# EveryCook_Mainboard.net
KiCad netlist of a schematic drawn in EAGLE
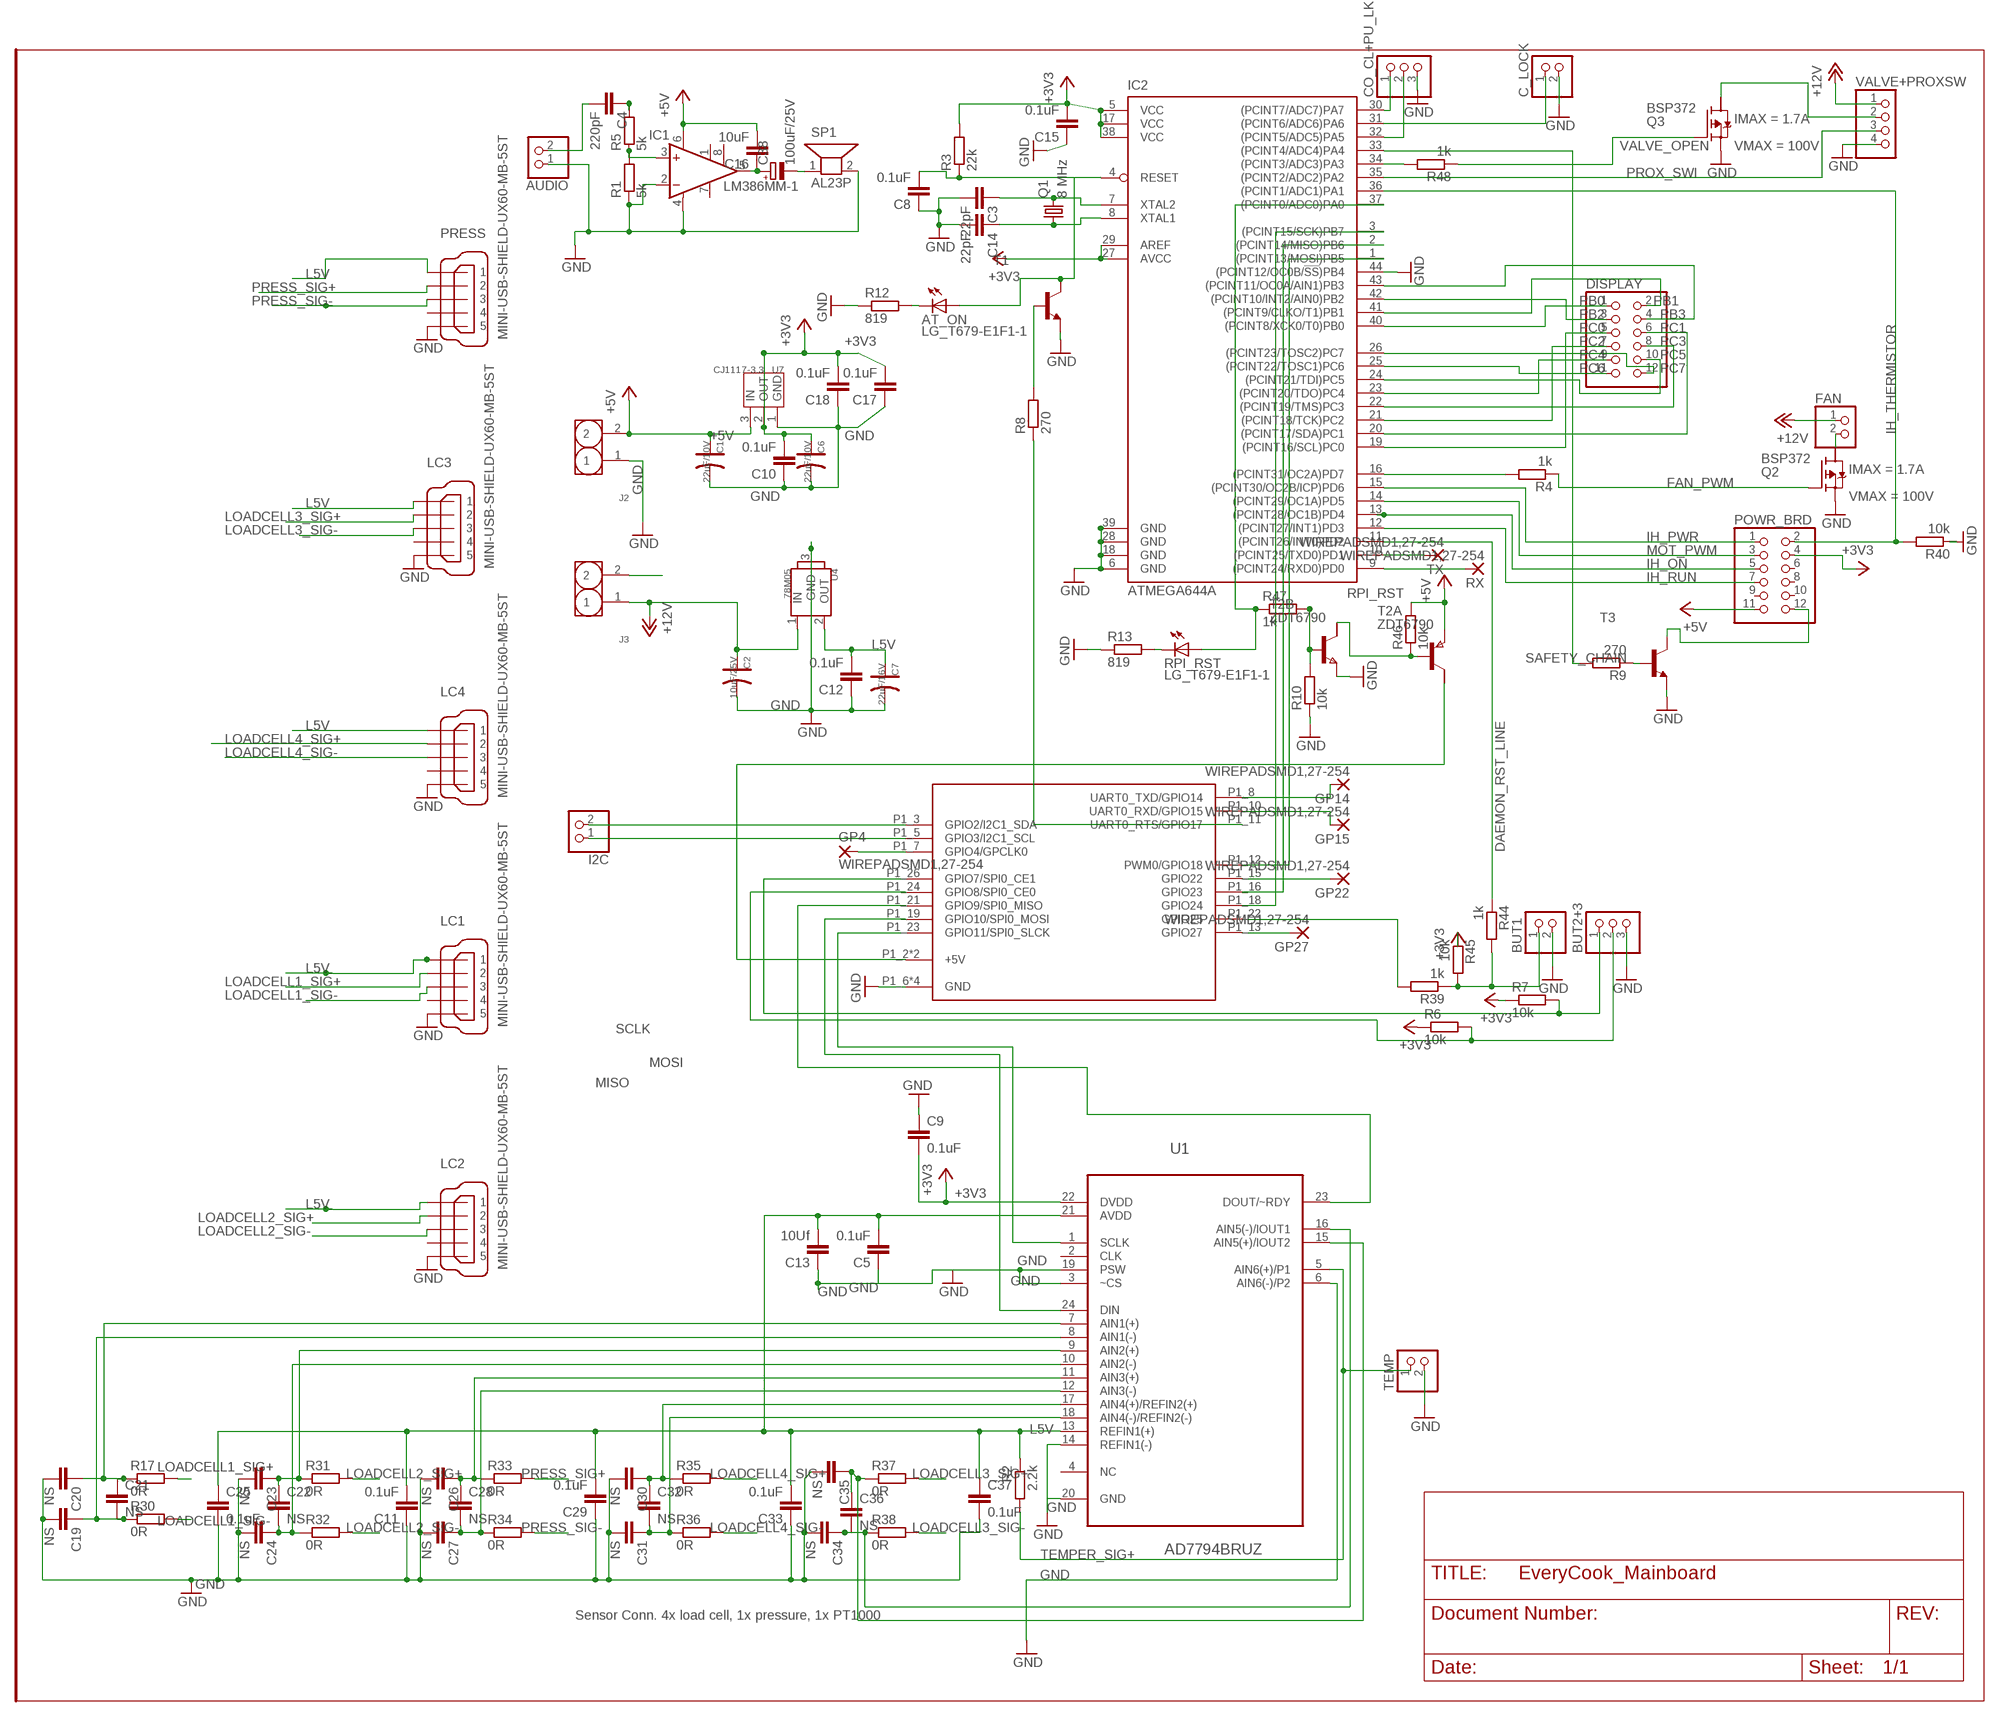
[diagram p0: schematic, sheet 1]

(export (version "E")
  (design (tool "Eeschema 10.0.6"))
  (components
    (comp (ref "AT_ON")
      (value "LG_T679-E1F1-1")
      (footprint "eagle-import:PLCC2")
      (libsource (lib "eagle-import") (part "_T679-?-1E1F1LG"))
    )
    (comp (ref "AUDIO")
      (value "PINHD-1X2")
      (footprint "eagle-import:1X02")
      (libsource (lib "eagle-import") (part "PINHD-1X2"))
    )
    (comp (ref "BUT1")
      (value "PINHD-1X2")
      (footprint "eagle-import:1X02")
      (libsource (lib "eagle-import") (part "PINHD-1X2"))
    )
    (comp (ref "BUT2+3")
      (value "PINHD-1X3")
      (footprint "eagle-import:1X03")
      (libsource (lib "eagle-import") (part "PINHD-1X3"))
    )
    (comp (ref "C1")
      (value "22uF/10V")
      (footprint "eagle-import:AVX-A")
      (libsource (lib "eagle-import") (part "CAP-AVX-A"))
    )
    (comp (ref "C2")
      (value "10uF/25V")
      (footprint "eagle-import:ELECTRO-SMD-B-4.8MM")
      (libsource (lib "eagle-import") (part "CAP-ELECTRO-B"))
    )
    (comp (ref "C3")
      (value "22pF")
      (footprint "eagle-import:C0805")
      (libsource (lib "eagle-import") (part "C-EUC0805"))
    )
    (comp (ref "C4")
      (value "220pF")
      (footprint "eagle-import:C0805")
      (libsource (lib "eagle-import") (part "C-EUC0805"))
    )
    (comp (ref "C5")
      (value "0.1uF")
      (footprint "eagle-import:C0805")
      (libsource (lib "eagle-import") (part "C-EUC0805"))
    )
    (comp (ref "C6")
      (value "22uF/10V")
      (footprint "eagle-import:AVX-A")
      (libsource (lib "eagle-import") (part "CAP-AVX-A"))
    )
    (comp (ref "C7")
      (value "22uF/16V")
      (footprint "eagle-import:ELECTRO-SMD-B-4.8MM")
      (libsource (lib "eagle-import") (part "CAP-ELECTRO-B"))
    )
    (comp (ref "C8")
      (value "0.1uF")
      (footprint "eagle-import:C0805")
      (libsource (lib "eagle-import") (part "C-EUC0805"))
    )
    (comp (ref "C9")
      (value "0.1uF")
      (footprint "eagle-import:C0805")
      (libsource (lib "eagle-import") (part "C-EUC0805"))
    )
    (comp (ref "C10")
      (value "0.1uF")
      (footprint "eagle-import:C0805")
      (libsource (lib "eagle-import") (part "C-EUC0805"))
    )
    (comp (ref "C11")
      (value "0.1uF")
      (footprint "eagle-import:C0805")
      (libsource (lib "eagle-import") (part "C-EUC0805"))
    )
    (comp (ref "C12")
      (value "0.1uF")
      (footprint "eagle-import:C0805")
      (libsource (lib "eagle-import") (part "C-EUC0805"))
    )
    (comp (ref "C13")
      (value "10Uf")
      (footprint "eagle-import:C0805")
      (libsource (lib "eagle-import") (part "C-EUC0805"))
    )
    (comp (ref "C14")
      (value "22pF")
      (footprint "eagle-import:C0805")
      (libsource (lib "eagle-import") (part "C-EUC0805"))
    )
    (comp (ref "C15")
      (value "0.1uF")
      (footprint "eagle-import:C0805")
      (libsource (lib "eagle-import") (part "C-EUC0805"))
    )
    (comp (ref "C16")
      (value "10uF")
      (footprint "eagle-import:C0805")
      (libsource (lib "eagle-import") (part "C-EUC0805"))
    )
    (comp (ref "C17")
      (value "0.1uF")
      (footprint "eagle-import:C0805")
      (libsource (lib "eagle-import") (part "C-EUC0805"))
    )
    (comp (ref "C18")
      (value "0.1uF")
      (footprint "eagle-import:C0805")
      (libsource (lib "eagle-import") (part "C-EUC0805"))
    )
    (comp (ref "C19")
      (value "NS")
      (footprint "eagle-import:C0805")
      (libsource (lib "eagle-import") (part "C-EUC0805"))
    )
    (comp (ref "C20")
      (value "NS")
      (footprint "eagle-import:C0805")
      (libsource (lib "eagle-import") (part "C-EUC0805"))
    )
    (comp (ref "C21")
      (value "NS")
      (footprint "eagle-import:C0805")
      (libsource (lib "eagle-import") (part "C-EUC0805"))
    )
    (comp (ref "C22")
      (value "NS")
      (footprint "eagle-import:C0805")
      (libsource (lib "eagle-import") (part "C-EUC0805"))
    )
    (comp (ref "C23")
      (value "NS")
      (footprint "eagle-import:C0805")
      (libsource (lib "eagle-import") (part "C-EUC0805"))
    )
    (comp (ref "C24")
      (value "NS")
      (footprint "eagle-import:C0805")
      (libsource (lib "eagle-import") (part "C-EUC0805"))
    )
    (comp (ref "C25")
      (value "0.1uF")
      (footprint "eagle-import:C0805")
      (libsource (lib "eagle-import") (part "C-EUC0805"))
    )
    (comp (ref "C26")
      (value "NS")
      (footprint "eagle-import:C0805")
      (libsource (lib "eagle-import") (part "C-EUC0805"))
    )
    (comp (ref "C27")
      (value "NS")
      (footprint "eagle-import:C0805")
      (libsource (lib "eagle-import") (part "C-EUC0805"))
    )
    (comp (ref "C28")
      (value "NS")
      (footprint "eagle-import:C0805")
      (libsource (lib "eagle-import") (part "C-EUC0805"))
    )
    (comp (ref "C29")
      (value "0.1uF")
      (footprint "eagle-import:C0805")
      (libsource (lib "eagle-import") (part "C-EUC0805"))
    )
    (comp (ref "C30")
      (value "NS")
      (footprint "eagle-import:C0805")
      (libsource (lib "eagle-import") (part "C-EUC0805"))
    )
    (comp (ref "C31")
      (value "NS")
      (footprint "eagle-import:C0805")
      (libsource (lib "eagle-import") (part "C-EUC0805"))
    )
    (comp (ref "C32")
      (value "NS")
      (footprint "eagle-import:C0805")
      (libsource (lib "eagle-import") (part "C-EUC0805"))
    )
    (comp (ref "C33")
      (value "0.1uF")
      (footprint "eagle-import:C0805")
      (libsource (lib "eagle-import") (part "C-EUC0805"))
    )
    (comp (ref "C34")
      (value "NS")
      (footprint "eagle-import:C0805")
      (libsource (lib "eagle-import") (part "C-EUC0805"))
    )
    (comp (ref "C35")
      (value "NS")
      (footprint "eagle-import:C0805")
      (libsource (lib "eagle-import") (part "C-EUC0805"))
    )
    (comp (ref "C36")
      (value "NS")
      (footprint "eagle-import:C0805")
      (libsource (lib "eagle-import") (part "C-EUC0805"))
    )
    (comp (ref "C37")
      (value "0.1uF")
      (footprint "eagle-import:C0805")
      (libsource (lib "eagle-import") (part "C-EUC0805"))
    )
    (comp (ref "C38")
      (value "100uF/25V")
      (footprint "eagle-import:UD-6,3X7,7_NICHICON")
      (libsource (lib "eagle-import") (part "CPOL-EUUD-6,3X7,7"))
    )
    (comp (ref "CO_CL+PU_LK")
      (value "PINHD-1X3")
      (footprint "eagle-import:1X03")
      (libsource (lib "eagle-import") (part "PINHD-1X3"))
    )
    (comp (ref "C_LOCK")
      (value "PINHD-1X2")
      (footprint "eagle-import:1X02")
      (libsource (lib "eagle-import") (part "PINHD-1X2"))
    )
    (comp (ref "DISPLAY")
      (value "PINHD-2X6")
      (footprint "eagle-import:2X06")
      (libsource (lib "eagle-import") (part "PINHD-2X6"))
    )
    (comp (ref "FAN")
      (value "PINHD-1X2")
      (footprint "eagle-import:1X02")
      (libsource (lib "eagle-import") (part "PINHD-1X2"))
    )
    (comp (ref "GP4")
      (value "WIREPADSMD1,27-254")
      (footprint "eagle-import:SMD1,27-2,54")
      (libsource (lib "eagle-import") (part "WIREPADSMD1,27-254"))
    )
    (comp (ref "GP14")
      (value "WIREPADSMD1,27-254")
      (footprint "eagle-import:SMD1,27-2,54")
      (libsource (lib "eagle-import") (part "WIREPADSMD1,27-254"))
    )
    (comp (ref "GP15")
      (value "WIREPADSMD1,27-254")
      (footprint "eagle-import:SMD1,27-2,54")
      (libsource (lib "eagle-import") (part "WIREPADSMD1,27-254"))
    )
    (comp (ref "GP22")
      (value "WIREPADSMD1,27-254")
      (footprint "eagle-import:SMD1,27-2,54")
      (libsource (lib "eagle-import") (part "WIREPADSMD1,27-254"))
    )
    (comp (ref "GP27")
      (value "WIREPADSMD1,27-254")
      (footprint "eagle-import:SMD1,27-2,54")
      (libsource (lib "eagle-import") (part "WIREPADSMD1,27-254"))
    )
    (comp (ref "I2C")
      (value "PINHD-1X2")
      (footprint "eagle-import:1X02")
      (libsource (lib "eagle-import") (part "PINHD-1X2"))
    )
    (comp (ref "IC1")
      (value "LM386MM-1")
      (footprint "eagle-import:MMSOP08")
      (libsource (lib "eagle-import") (part "LM386?-MM1"))
    )
    (comp (ref "IC2")
      (value "ATMEGA644A")
      (footprint "eagle-import:TQFP44")
      (fields (field (name "MPN") "ATMEGA644PV-10AU"))
      (libsource (lib "eagle-import") (part "ATMEGA644A"))
    )
    (comp (ref "J2")
      (value "HEADER-2P-5.0")
      (footprint "eagle-import:2P-5.0")
      (libsource (lib "eagle-import") (part "HEADER-2P-5.0"))
    )
    (comp (ref "J3")
      (value "HEADER-2P-5.0")
      (footprint "eagle-import:2P-5.0")
      (libsource (lib "eagle-import") (part "HEADER-2P-5.0"))
    )
    (comp (ref "LC1")
      (value "MINI-USB-SHIELD-UX60-MB-5ST")
      (footprint "eagle-import:UX60-MB-5ST")
      (libsource (lib "eagle-import") (part "MINI-USB-SHIELD-UX60-MB-5ST"))
    )
    (comp (ref "LC2")
      (value "MINI-USB-SHIELD-UX60-MB-5ST")
      (footprint "eagle-import:UX60-MB-5ST")
      (libsource (lib "eagle-import") (part "MINI-USB-SHIELD-UX60-MB-5ST"))
    )
    (comp (ref "LC3")
      (value "MINI-USB-SHIELD-UX60-MB-5ST")
      (footprint "eagle-import:UX60-MB-5ST")
      (libsource (lib "eagle-import") (part "MINI-USB-SHIELD-UX60-MB-5ST"))
    )
    (comp (ref "LC4")
      (value "MINI-USB-SHIELD-UX60-MB-5ST")
      (footprint "eagle-import:UX60-MB-5ST")
      (libsource (lib "eagle-import") (part "MINI-USB-SHIELD-UX60-MB-5ST"))
    )
    (comp (ref "POWR_BRD")
      (value "PINHD-2X6")
      (footprint "eagle-import:2X06")
      (libsource (lib "eagle-import") (part "PINHD-2X6"))
    )
    (comp (ref "PRESS")
      (value "MINI-USB-SHIELD-UX60-MB-5ST")
      (footprint "eagle-import:UX60-MB-5ST")
      (libsource (lib "eagle-import") (part "MINI-USB-SHIELD-UX60-MB-5ST"))
    )
    (comp (ref "Q1")
      (value "8 MHz")
      (footprint "eagle-import:HC49UP")
      (libsource (lib "eagle-import") (part "CRYSTALHC49UP"))
    )
    (comp (ref "Q2")
      (value "BSP372")
      (footprint "eagle-import:PG-SOT-223")
      (fields (field (name "IMAX") "1.7A") (field (name "MF") "Infineon") (field (name "VMAX") "100V"))
      (libsource (lib "eagle-import") (part "BSP613P"))
    )
    (comp (ref "Q3")
      (value "BSP372")
      (footprint "eagle-import:PG-SOT-223")
      (fields (field (name "IMAX") "1.7A") (field (name "MF") "Infineon") (field (name "VMAX") "100V"))
      (libsource (lib "eagle-import") (part "BSP613P"))
    )
    (comp (ref "R1")
      (value "5k")
      (footprint "eagle-import:R0805")
      (libsource (lib "eagle-import") (part "R-EU_R0805"))
    )
    (comp (ref "R2")
      (value "2.2k")
      (footprint "eagle-import:R0805")
      (libsource (lib "eagle-import") (part "R-EU_R0805"))
    )
    (comp (ref "R3")
      (value "22k")
      (footprint "eagle-import:R0805")
      (libsource (lib "eagle-import") (part "R-EU_R0805"))
    )
    (comp (ref "R4")
      (value "1k")
      (footprint "eagle-import:R0805")
      (libsource (lib "eagle-import") (part "R-EU_R0805"))
    )
    (comp (ref "R5")
      (value "5k")
      (footprint "eagle-import:R0805")
      (libsource (lib "eagle-import") (part "R-EU_R0805"))
    )
    (comp (ref "R6")
      (value "10k")
      (footprint "eagle-import:R0805")
      (libsource (lib "eagle-import") (part "R-EU_R0805"))
    )
    (comp (ref "R7")
      (value "10k")
      (footprint "eagle-import:R0805")
      (libsource (lib "eagle-import") (part "R-EU_R0805"))
    )
    (comp (ref "R8")
      (value "270")
      (footprint "eagle-import:R0805")
      (libsource (lib "eagle-import") (part "R-EU_R0805"))
    )
    (comp (ref "R9")
      (value "270")
      (footprint "eagle-import:R0805")
      (libsource (lib "eagle-import") (part "R-EU_R0805"))
    )
    (comp (ref "R10")
      (value "10k")
      (footprint "eagle-import:R0805")
      (libsource (lib "eagle-import") (part "R-EU_R0805"))
    )
    (comp (ref "R12")
      (value "819")
      (footprint "eagle-import:R0805")
      (libsource (lib "eagle-import") (part "R-EU_R0805"))
    )
    (comp (ref "R13")
      (value "819")
      (footprint "eagle-import:R0805")
      (libsource (lib "eagle-import") (part "R-EU_R0805"))
    )
    (comp (ref "R17")
      (value "0R")
      (footprint "eagle-import:R0805")
      (libsource (lib "eagle-import") (part "R-EU_R0805"))
    )
    (comp (ref "R30")
      (value "0R")
      (footprint "eagle-import:R0805")
      (libsource (lib "eagle-import") (part "R-EU_R0805"))
    )
    (comp (ref "R31")
      (value "0R")
      (footprint "eagle-import:R0805")
      (libsource (lib "eagle-import") (part "R-EU_R0805"))
    )
    (comp (ref "R32")
      (value "0R")
      (footprint "eagle-import:R0805")
      (libsource (lib "eagle-import") (part "R-EU_R0805"))
    )
    (comp (ref "R33")
      (value "0R")
      (footprint "eagle-import:R0805")
      (libsource (lib "eagle-import") (part "R-EU_R0805"))
    )
    (comp (ref "R34")
      (value "0R")
      (footprint "eagle-import:R0805")
      (libsource (lib "eagle-import") (part "R-EU_R0805"))
    )
    (comp (ref "R35")
      (value "0R")
      (footprint "eagle-import:R0805")
      (libsource (lib "eagle-import") (part "R-EU_R0805"))
    )
    (comp (ref "R36")
      (value "0R")
      (footprint "eagle-import:R0805")
      (libsource (lib "eagle-import") (part "R-EU_R0805"))
    )
    (comp (ref "R37")
      (value "0R")
      (footprint "eagle-import:R0805")
      (libsource (lib "eagle-import") (part "R-EU_R0805"))
    )
    (comp (ref "R38")
      (value "0R")
      (footprint "eagle-import:R0805")
      (libsource (lib "eagle-import") (part "R-EU_R0805"))
    )
    (comp (ref "R39")
      (value "1k")
      (footprint "eagle-import:R0805")
      (libsource (lib "eagle-import") (part "R-EU_R0805"))
    )
    (comp (ref "R40")
      (value "10k")
      (footprint "eagle-import:R0805")
      (libsource (lib "eagle-import") (part "R-EU_R0805"))
    )
    (comp (ref "R44")
      (value "1k")
      (footprint "eagle-import:R0805")
      (libsource (lib "eagle-import") (part "R-EU_R0805"))
    )
    (comp (ref "R45")
      (value "10k")
      (footprint "eagle-import:R0805")
      (libsource (lib "eagle-import") (part "R-EU_R0805"))
    )
    (comp (ref "R46")
      (value "10k")
      (footprint "eagle-import:R0805")
      (libsource (lib "eagle-import") (part "R-EU_R0805"))
    )
    (comp (ref "R47")
      (value "1k")
      (footprint "eagle-import:R0805")
      (libsource (lib "eagle-import") (part "R-EU_R0805"))
    )
    (comp (ref "R48")
      (value "1k")
      (footprint "eagle-import:R0805")
      (libsource (lib "eagle-import") (part "R-EU_R0805"))
    )
    (comp (ref "RPI_RST")
      (value "LG_T679-E1F1-1")
      (footprint "eagle-import:PLCC2")
      (libsource (lib "eagle-import") (part "_T679-?-1E1F1LG"))
    )
    (comp (ref "RX")
      (value "WIREPADSMD1,27-254")
      (footprint "eagle-import:SMD1,27-2,54")
      (libsource (lib "eagle-import") (part "WIREPADSMD1,27-254"))
    )
    (comp (ref "SP1")
      (value "AL23P")
      (footprint "eagle-import:AL23P")
      (libsource (lib "eagle-import") (part "AL23P"))
    )
    (comp (ref "T1")
      (value "MMBT2222ALT1-NPN-SOT23-BEC")
      (footprint "eagle-import:SOT23-BEC")
      (libsource (lib "eagle-import") (part "-NPN-SOT23-BECMMBT2222ALT1"))
    )
    (comp (ref "T2")
      (value "ZDT6790")
      (footprint "eagle-import:SM8")
      (libsource (lib "eagle-import") (part "NPN_PNPSM8"))
    )
    (comp (ref "T3")
      (value "MMBT2222ALT1-NPN-SOT23-BEC")
      (footprint "eagle-import:SOT23-BEC")
      (libsource (lib "eagle-import") (part "-NPN-SOT23-BECMMBT2222ALT1"))
    )
    (comp (ref "TEMP")
      (value "PINHD-1X2")
      (footprint "eagle-import:1X02")
      (libsource (lib "eagle-import") (part "PINHD-1X2"))
    )
    (comp (ref "TX")
      (value "WIREPADSMD1,27-254")
      (footprint "eagle-import:SMD1,27-2,54")
      (libsource (lib "eagle-import") (part "WIREPADSMD1,27-254"))
    )
    (comp (ref "U$5")
      (value "RPI-B-V2")
      (footprint "eagle-import:RPI-B-V2")
      (libsource (lib "eagle-import") (part "RPI-B-V2"))
    )
    (comp (ref "U1")
      (value "AD7794BRUZ")
      (footprint "eagle-import:SOP65P640X120-24N")
      (libsource (lib "eagle-import") (part "AD7794BRUZ"))
    )
    (comp (ref "U4")
      (value "78M05")
      (footprint "eagle-import:TO252")
      (libsource (lib "eagle-import") (part "78M05-TO252"))
    )
    (comp (ref "U7")
      (value "CJ1117-3.3")
      (footprint "eagle-import:SOT89")
      (libsource (lib "eagle-import") (part "LD1117SOT89"))
    )
    (comp (ref "VALVE+PROXSW")
      (value "PINHD-1X4")
      (footprint "eagle-import:1X04")
      (libsource (lib "eagle-import") (part "PINHD-1X4"))
    )
  )
  (nets
    (net (code "1") (name "+3V3") (class "Default")
      (node (ref "C10") (pin "2") (pinfunction "2_2") (pintype "passive"))
      (node (ref "C15") (pin "2") (pinfunction "2_2") (pintype "passive"))
      (node (ref "C17") (pin "2") (pinfunction "2_2") (pintype "passive"))
      (node (ref "C18") (pin "2") (pinfunction "2_2") (pintype "passive"))
      (node (ref "C6") (pin "+") (pinfunction "+_+") (pintype "passive"))
      (node (ref "C9") (pin "2") (pinfunction "2_2") (pintype "passive"))
      (node (ref "IC2") (pin "17") (pinfunction "VCC_17") (pintype "power_in"))
      (node (ref "IC2") (pin "27") (pinfunction "AVCC_27") (pintype "power_in"))
      (node (ref "IC2") (pin "29") (pinfunction "AREF_29") (pintype "passive"))
      (node (ref "IC2") (pin "38") (pinfunction "VCC_38") (pintype "power_in"))
      (node (ref "IC2") (pin "5") (pinfunction "VCC_5") (pintype "power_in"))
      (node (ref "POWR_BRD") (pin "4") (pinfunction "4_4") (pintype "passive"))
      (node (ref "R3") (pin "2") (pinfunction "2_2") (pintype "passive"))
      (node (ref "R45") (pin "1") (pinfunction "1_1") (pintype "passive"))
      (node (ref "R6") (pin "1") (pinfunction "1_1") (pintype "passive"))
      (node (ref "R7") (pin "1") (pinfunction "1_1") (pintype "passive"))
      (node (ref "U1") (pin "22") (pinfunction "DVDD_22") (pintype "power_in"))
      (node (ref "U7") (pin "2") (pinfunction "OUT_2") (pintype "bidirectional"))
      (node (ref "U7") (pin "4") (pinfunction "TAB_4") (pintype "bidirectional"))
    )
    (net (code "2") (name "+5V") (class "Default")
      (node (ref "C1") (pin "+") (pinfunction "+_+") (pintype "passive"))
      (node (ref "C16") (pin "2") (pinfunction "2_2") (pintype "passive"))
      (node (ref "IC1") (pin "6") (pinfunction "VS_6") (pintype "power_in"))
      (node (ref "J2") (pin "2") (pinfunction "2_2") (pintype "bidirectional"))
      (node (ref "POWR_BRD") (pin "11") (pinfunction "11_11") (pintype "passive"))
      (node (ref "R46") (pin "2") (pinfunction "2_2") (pintype "passive"))
      (node (ref "T2") (pin "1") (pinfunction "E_1") (pintype "passive"))
      (node (ref "U7") (pin "3") (pinfunction "IN_3") (pintype "bidirectional"))
    )
    (net (code "3") (name "+12V") (class "Default")
      (node (ref "C2") (pin "+") (pinfunction "+_+") (pintype "passive"))
      (node (ref "FAN") (pin "1") (pinfunction "1_1") (pintype "passive"))
      (node (ref "J3") (pin "1") (pinfunction "1_1") (pintype "bidirectional"))
      (node (ref "U4") (pin "1") (pinfunction "IN_1") (pintype "bidirectional"))
      (node (ref "VALVE+PROXSW") (pin "1") (pinfunction "1_1") (pintype "passive"))
    )
    (net (code "4") (name "/DAEMON_RST_LINE") (class "Default")
      (node (ref "IC2") (pin "11") (pinfunction "(PCINT26/INT0)PD2_11") (pintype "bidirectional"))
      (node (ref "R44") (pin "1") (pinfunction "1_1") (pintype "passive"))
    )
    (net (code "5") (name "/FAN_PWM") (class "Default")
      (node (ref "Q2") (pin "1") (pinfunction "G_1") (pintype "passive"))
      (node (ref "R4") (pin "1") (pinfunction "1_1") (pintype "passive"))
    )
    (net (code "6") (name "/IH_ON") (class "Default")
      (node (ref "IC2") (pin "13") (pinfunction "(PCINT28/OC1B)PD4_13") (pintype "bidirectional"))
      (node (ref "POWR_BRD") (pin "5") (pinfunction "5_5") (pintype "passive"))
    )
    (net (code "7") (name "/IH_PWR") (class "Default")
      (node (ref "IC2") (pin "15") (pinfunction "(PCINT30/OC2B/ICP)PD6_15") (pintype "bidirectional"))
      (node (ref "POWR_BRD") (pin "1") (pinfunction "1_1") (pintype "passive"))
    )
    (net (code "8") (name "/IH_RUN") (class "Default")
      (node (ref "IC2") (pin "12") (pinfunction "(PCINT27/INT1)PD3_12") (pintype "bidirectional"))
      (node (ref "POWR_BRD") (pin "7") (pinfunction "7_7") (pintype "passive"))
    )
    (net (code "9") (name "/IH_THERMISTOR") (class "Default")
      (node (ref "IC2") (pin "36") (pinfunction "(PCINT1/ADC1)PA1_36") (pintype "bidirectional"))
      (node (ref "POWR_BRD") (pin "2") (pinfunction "2_2") (pintype "passive"))
      (node (ref "R40") (pin "2") (pinfunction "2_2") (pintype "passive"))
    )
    (net (code "10") (name "/L5V") (class "Default")
      (node (ref "C11") (pin "2") (pinfunction "2_2") (pintype "passive"))
      (node (ref "C12") (pin "2") (pinfunction "2_2") (pintype "passive"))
      (node (ref "C13") (pin "2") (pinfunction "2_2") (pintype "passive"))
      (node (ref "C25") (pin "1") (pinfunction "1_1") (pintype "passive"))
      (node (ref "C29") (pin "2") (pinfunction "2_2") (pintype "passive"))
      (node (ref "C33") (pin "2") (pinfunction "2_2") (pintype "passive"))
      (node (ref "C37") (pin "1") (pinfunction "1_1") (pintype "passive"))
      (node (ref "C5") (pin "2") (pinfunction "2_2") (pintype "passive"))
      (node (ref "C7") (pin "+") (pinfunction "+_+") (pintype "passive"))
      (node (ref "LC1") (pin "1") (pinfunction "1_1") (pintype "input"))
      (node (ref "LC2") (pin "1") (pinfunction "1_1") (pintype "input"))
      (node (ref "LC3") (pin "1") (pinfunction "1_1") (pintype "input"))
      (node (ref "LC4") (pin "1") (pinfunction "1_1") (pintype "input"))
      (node (ref "PRESS") (pin "1") (pinfunction "1_1") (pintype "input"))
      (node (ref "R2") (pin "1") (pinfunction "1_1") (pintype "passive"))
      (node (ref "U1") (pin "13") (pinfunction "REFIN1(+)_13") (pintype "input"))
      (node (ref "U1") (pin "21") (pinfunction "AVDD_21") (pintype "power_in"))
      (node (ref "U4") (pin "2") (pinfunction "OUT_2") (pintype "bidirectional"))
    )
    (net (code "11") (name "/LOADCELL1_SIG+") (class "Default")
      (node (ref "LC1") (pin "2") (pinfunction "2_2") (pintype "input"))
      (node (ref "R17") (pin "2") (pinfunction "2_2") (pintype "passive"))
    )
    (net (code "12") (name "/LOADCELL1_SIG-") (class "Default")
      (node (ref "LC1") (pin "3") (pinfunction "3_3") (pintype "input"))
      (node (ref "R30") (pin "2") (pinfunction "2_2") (pintype "passive"))
    )
    (net (code "13") (name "/LOADCELL2_SIG+") (class "Default")
      (node (ref "LC2") (pin "2") (pinfunction "2_2") (pintype "input"))
      (node (ref "R31") (pin "2") (pinfunction "2_2") (pintype "passive"))
    )
    (net (code "14") (name "/LOADCELL2_SIG-") (class "Default")
      (node (ref "LC2") (pin "3") (pinfunction "3_3") (pintype "input"))
      (node (ref "R32") (pin "2") (pinfunction "2_2") (pintype "passive"))
    )
    (net (code "15") (name "/LOADCELL3_SIG+") (class "Default")
      (node (ref "LC3") (pin "2") (pinfunction "2_2") (pintype "input"))
      (node (ref "R37") (pin "2") (pinfunction "2_2") (pintype "passive"))
    )
    (net (code "16") (name "/LOADCELL3_SIG-") (class "Default")
      (node (ref "LC3") (pin "3") (pinfunction "3_3") (pintype "input"))
      (node (ref "R38") (pin "2") (pinfunction "2_2") (pintype "passive"))
    )
    (net (code "17") (name "/LOADCELL4_SIG+") (class "Default")
      (node (ref "LC4") (pin "2") (pinfunction "2_2") (pintype "input"))
      (node (ref "R35") (pin "2") (pinfunction "2_2") (pintype "passive"))
    )
    (net (code "18") (name "/LOADCELL4_SIG-") (class "Default")
      (node (ref "LC4") (pin "3") (pinfunction "3_3") (pintype "input"))
      (node (ref "R36") (pin "2") (pinfunction "2_2") (pintype "passive"))
    )
    (net (code "19") (name "/MISO") (class "Default")
      (node (ref "U$5") (pin "P1_21") (pinfunction "GPIO9/SPI0_MISO_P1_21") (pintype "bidirectional"))
      (node (ref "U1") (pin "23") (pinfunction "DOUT/~{RDY}_23") (pintype "bidirectional"))
    )
    (net (code "20") (name "/MOSI") (class "Default")
      (node (ref "U$5") (pin "P1_19") (pinfunction "GPIO10/SPI0_MOSI_P1_19") (pintype "bidirectional"))
      (node (ref "U1") (pin "24") (pinfunction "DIN_24") (pintype "input"))
    )
    (net (code "21") (name "/MOT_PWM") (class "Default")
      (node (ref "IC2") (pin "14") (pinfunction "(PCINT29/OC1A)PD5_14") (pintype "bidirectional"))
      (node (ref "POWR_BRD") (pin "3") (pinfunction "3_3") (pintype "passive"))
    )
    (net (code "22") (name "/PB0") (class "Default")
      (node (ref "DISPLAY") (pin "1") (pinfunction "1_1") (pintype "passive"))
      (node (ref "IC2") (pin "40") (pinfunction "(PCINT8/XCK0/T0)PB0_40") (pintype "bidirectional"))
    )
    (net (code "23") (name "/PB1") (class "Default")
      (node (ref "DISPLAY") (pin "2") (pinfunction "2_2") (pintype "passive"))
      (node (ref "IC2") (pin "41") (pinfunction "(PCINT9/CLKO/T1)PB1_41") (pintype "bidirectional"))
    )
    (net (code "24") (name "/PB2") (class "Default")
      (node (ref "DISPLAY") (pin "3") (pinfunction "3_3") (pintype "passive"))
      (node (ref "IC2") (pin "42") (pinfunction "(PCINT10/INT2/AIN0)PB2_42") (pintype "bidirectional"))
    )
    (net (code "25") (name "/PB3") (class "Default")
      (node (ref "DISPLAY") (pin "4") (pinfunction "4_4") (pintype "passive"))
      (node (ref "IC2") (pin "43") (pinfunction "(PCINT11/OC0A/AIN1)PB3_43") (pintype "bidirectional"))
    )
    (net (code "26") (name "/PC0") (class "Default")
      (node (ref "DISPLAY") (pin "5") (pinfunction "5_5") (pintype "passive"))
      (node (ref "IC2") (pin "19") (pinfunction "(PCINT16/SCL)PC0_19") (pintype "output"))
    )
    (net (code "27") (name "/PC1") (class "Default")
      (node (ref "DISPLAY") (pin "6") (pinfunction "6_6") (pintype "passive"))
      (node (ref "IC2") (pin "20") (pinfunction "(PCINT17/SDA)PC1_20") (pintype "output"))
    )
    (net (code "28") (name "/PC2") (class "Default")
      (node (ref "DISPLAY") (pin "7") (pinfunction "7_7") (pintype "passive"))
      (node (ref "IC2") (pin "21") (pinfunction "(PCINT18/TCK)PC2_21") (pintype "output"))
    )
    (net (code "29") (name "/PC3") (class "Default")
      (node (ref "DISPLAY") (pin "8") (pinfunction "8_8") (pintype "passive"))
      (node (ref "IC2") (pin "22") (pinfunction "(PCINT19/TMS)PC3_22") (pintype "output"))
    )
    (net (code "30") (name "/PC4") (class "Default")
      (node (ref "DISPLAY") (pin "9") (pinfunction "9_9") (pintype "passive"))
      (node (ref "IC2") (pin "23") (pinfunction "(PCINT20/TDO)PC4_23") (pintype "output"))
    )
    (net (code "31") (name "/PC5") (class "Default")
      (node (ref "DISPLAY") (pin "10") (pinfunction "10_10") (pintype "passive"))
      (node (ref "IC2") (pin "24") (pinfunction "(PCINT21/TDI)PC5_24") (pintype "output"))
    )
    (net (code "32") (name "/PC6") (class "Default")
      (node (ref "DISPLAY") (pin "11") (pinfunction "11_11") (pintype "passive"))
      (node (ref "IC2") (pin "25") (pinfunction "(PCINT22/TOSC1)PC6_25") (pintype "output"))
    )
    (net (code "33") (name "/PC7") (class "Default")
      (node (ref "DISPLAY") (pin "12") (pinfunction "12_12") (pintype "passive"))
      (node (ref "IC2") (pin "26") (pinfunction "(PCINT23/TOSC2)PC7_26") (pintype "output"))
    )
    (net (code "34") (name "/PRESS_SIG+") (class "Default")
      (node (ref "PRESS") (pin "2") (pinfunction "2_2") (pintype "input"))
      (node (ref "R33") (pin "2") (pinfunction "2_2") (pintype "passive"))
    )
    (net (code "35") (name "/PRESS_SIG-") (class "Default")
      (node (ref "PRESS") (pin "3") (pinfunction "3_3") (pintype "input"))
      (node (ref "R34") (pin "2") (pinfunction "2_2") (pintype "passive"))
    )
    (net (code "36") (name "/PROX_SWI") (class "Default")
      (node (ref "IC2") (pin "35") (pinfunction "(PCINT2/ADC2)PA2_35") (pintype "bidirectional"))
      (node (ref "VALVE+PROXSW") (pin "3") (pinfunction "3_3") (pintype "passive"))
    )
    (net (code "37") (name "/RPI_RST") (class "Default")
      (node (ref "IC2") (pin "37") (pinfunction "(PCINT0/ADC0)PA0_37") (pintype "bidirectional"))
      (node (ref "R47") (pin "1") (pinfunction "1_1") (pintype "passive"))
      (node (ref "RPI_RST") (pin "A") (pinfunction "A_A") (pintype "passive"))
    )
    (net (code "38") (name "/SAFETY_CHAIN") (class "Default")
      (node (ref "IC2") (pin "33") (pinfunction "(PCINT4/ADC4)PA4_33") (pintype "bidirectional"))
      (node (ref "R9") (pin "2") (pinfunction "2_2") (pintype "passive"))
    )
    (net (code "39") (name "/SCLK") (class "Default")
      (node (ref "U$5") (pin "P1_23") (pinfunction "GPIO11/SPI0_SLCK_P1_23") (pintype "bidirectional"))
      (node (ref "U1") (pin "1") (pinfunction "SCLK_1") (pintype "input"))
    )
    (net (code "40") (name "/TEMPER_SIG+") (class "Default")
      (node (ref "R2") (pin "2") (pinfunction "2_2") (pintype "passive"))
      (node (ref "TEMP") (pin "1") (pinfunction "1_1") (pintype "passive"))
      (node (ref "U1") (pin "5") (pinfunction "AIN6(+)/P1_5") (pintype "bidirectional"))
    )
    (net (code "41") (name "/VALVE_OPEN") (class "Default")
      (node (ref "Q3") (pin "1") (pinfunction "G_1") (pintype "passive"))
      (node (ref "R48") (pin "1") (pinfunction "1_1") (pintype "passive"))
    )
    (net (code "42") (name "GND") (class "Default")
      (node (ref "AUDIO") (pin "1") (pinfunction "1_1") (pintype "passive"))
      (node (ref "BUT1") (pin "2") (pinfunction "2_2") (pintype "passive"))
      (node (ref "BUT2+3") (pin "3") (pinfunction "3_3") (pintype "passive"))
      (node (ref "C1") (pin "-") (pinfunction "-_-") (pintype "passive"))
      (node (ref "C10") (pin "1") (pinfunction "1_1") (pintype "passive"))
      (node (ref "C11") (pin "1") (pinfunction "1_1") (pintype "passive"))
      (node (ref "C12") (pin "1") (pinfunction "1_1") (pintype "passive"))
      (node (ref "C13") (pin "1") (pinfunction "1_1") (pintype "passive"))
      (node (ref "C14") (pin "2") (pinfunction "2_2") (pintype "passive"))
      (node (ref "C15") (pin "1") (pinfunction "1_1") (pintype "passive"))
      (node (ref "C17") (pin "1") (pinfunction "1_1") (pintype "passive"))
      (node (ref "C18") (pin "1") (pinfunction "1_1") (pintype "passive"))
      (node (ref "C19") (pin "2") (pinfunction "2_2") (pintype "passive"))
      (node (ref "C2") (pin "-") (pinfunction "-_-") (pintype "passive"))
      (node (ref "C20") (pin "2") (pinfunction "2_2") (pintype "passive"))
      (node (ref "C23") (pin "2") (pinfunction "2_2") (pintype "passive"))
      (node (ref "C24") (pin "2") (pinfunction "2_2") (pintype "passive"))
      (node (ref "C25") (pin "2") (pinfunction "2_2") (pintype "passive"))
      (node (ref "C26") (pin "2") (pinfunction "2_2") (pintype "passive"))
      (node (ref "C27") (pin "2") (pinfunction "2_2") (pintype "passive"))
      (node (ref "C29") (pin "1") (pinfunction "1_1") (pintype "passive"))
      (node (ref "C3") (pin "2") (pinfunction "2_2") (pintype "passive"))
      (node (ref "C30") (pin "2") (pinfunction "2_2") (pintype "passive"))
      (node (ref "C31") (pin "2") (pinfunction "2_2") (pintype "passive"))
      (node (ref "C33") (pin "1") (pinfunction "1_1") (pintype "passive"))
      (node (ref "C34") (pin "2") (pinfunction "2_2") (pintype "passive"))
      (node (ref "C35") (pin "2") (pinfunction "2_2") (pintype "passive"))
      (node (ref "C37") (pin "2") (pinfunction "2_2") (pintype "passive"))
      (node (ref "C5") (pin "1") (pinfunction "1_1") (pintype "passive"))
      (node (ref "C6") (pin "-") (pinfunction "-_-") (pintype "passive"))
      (node (ref "C7") (pin "-") (pinfunction "-_-") (pintype "passive"))
      (node (ref "C8") (pin "1") (pinfunction "1_1") (pintype "passive"))
      (node (ref "C9") (pin "1") (pinfunction "1_1") (pintype "passive"))
      (node (ref "CO_CL+PU_LK") (pin "3") (pinfunction "3_3") (pintype "passive"))
      (node (ref "C_LOCK") (pin "2") (pinfunction "2_2") (pintype "passive"))
      (node (ref "IC1") (pin "2") (pinfunction "-IN_2") (pintype "input"))
      (node (ref "IC1") (pin "4") (pinfunction "GND_4") (pintype "power_in"))
      (node (ref "IC2") (pin "18") (pinfunction "GND_18") (pintype "power_in"))
      (node (ref "IC2") (pin "28") (pinfunction "GND_28") (pintype "power_in"))
      (node (ref "IC2") (pin "39") (pinfunction "GND_39") (pintype "power_in"))
      (node (ref "IC2") (pin "44") (pinfunction "(PCINT12/OC0B/~{SS})PB4_44") (pintype "bidirectional"))
      (node (ref "IC2") (pin "6") (pinfunction "GND_6") (pintype "power_in"))
      (node (ref "J2") (pin "1") (pinfunction "1_1") (pintype "bidirectional"))
      (node (ref "LC1") (pin "5") (pinfunction "5_5") (pintype "input"))
      (node (ref "LC2") (pin "5") (pinfunction "5_5") (pintype "input"))
      (node (ref "LC3") (pin "5") (pinfunction "5_5") (pintype "input"))
      (node (ref "LC4") (pin "5") (pinfunction "5_5") (pintype "input"))
      (node (ref "PRESS") (pin "5") (pinfunction "5_5") (pintype "input"))
      (node (ref "Q2") (pin "3") (pinfunction "S_3") (pintype "passive"))
      (node (ref "Q3") (pin "3") (pinfunction "S_3") (pintype "passive"))
      (node (ref "R1") (pin "1") (pinfunction "1_1") (pintype "passive"))
      (node (ref "R10") (pin "1") (pinfunction "1_1") (pintype "passive"))
      (node (ref "R12") (pin "1") (pinfunction "1_1") (pintype "passive"))
      (node (ref "R13") (pin "1") (pinfunction "1_1") (pintype "passive"))
      (node (ref "R40") (pin "1") (pinfunction "1_1") (pintype "passive"))
      (node (ref "SP1") (pin "2") (pinfunction "2_2") (pintype "passive"))
      (node (ref "T1") (pin "E") (pinfunction "E_E") (pintype "passive"))
      (node (ref "T2") (pin "3") (pinfunction "E_3") (pintype "passive"))
      (node (ref "T3") (pin "E") (pinfunction "E_E") (pintype "passive"))
      (node (ref "TEMP") (pin "2") (pinfunction "2_2") (pintype "passive"))
      (node (ref "U$5") (pin "P1_14") (pinfunction "GND_P1_14") (pintype "power_in"))
      (node (ref "U$5") (pin "P1_20") (pinfunction "GND_P1_20") (pintype "power_in"))
      (node (ref "U$5") (pin "P1_25") (pinfunction "GND_P1_25") (pintype "power_in"))
      (node (ref "U$5") (pin "P1_6") (pinfunction "GND_P1_6") (pintype "power_in"))
      (node (ref "U1") (pin "14") (pinfunction "REFIN1(-)_14") (pintype "input"))
      (node (ref "U1") (pin "19") (pinfunction "PSW_19") (pintype "passive"))
      (node (ref "U1") (pin "20") (pinfunction "GND_20") (pintype "passive"))
      (node (ref "U1") (pin "3") (pinfunction "~{CS}_3") (pintype "input"))
      (node (ref "U1") (pin "6") (pinfunction "AIN6(-)/P2_6") (pintype "bidirectional"))
      (node (ref "U4") (pin "3") (pinfunction "GND_3") (pintype "bidirectional"))
      (node (ref "U7") (pin "1") (pinfunction "GND_1") (pintype "bidirectional"))
      (node (ref "VALVE+PROXSW") (pin "4") (pinfunction "4_4") (pintype "passive"))
    )
    (net (code "43") (name "Net-(AT_ON-PadC)") (class "Default")
      (node (ref "AT_ON") (pin "C") (pinfunction "C_C") (pintype "passive"))
      (node (ref "R12") (pin "2") (pinfunction "2_2") (pintype "passive"))
    )
    (net (code "44") (name "Net-(AUDIO-Pad2)") (class "Default")
      (node (ref "AUDIO") (pin "2") (pinfunction "2_2") (pintype "passive"))
      (node (ref "C4") (pin "2") (pinfunction "2_2") (pintype "passive"))
    )
    (net (code "45") (name "Net-(BUT1-Pad1)") (class "Default")
      (node (ref "BUT1") (pin "1") (pinfunction "1_1") (pintype "passive"))
      (node (ref "R39") (pin "1") (pinfunction "1_1") (pintype "passive"))
      (node (ref "R44") (pin "2") (pinfunction "2_2") (pintype "passive"))
      (node (ref "R45") (pin "2") (pinfunction "2_2") (pintype "passive"))
    )
    (net (code "46") (name "Net-(C4-Pad1)") (class "Default")
      (node (ref "C4") (pin "1") (pinfunction "1_1") (pintype "passive"))
      (node (ref "R5") (pin "2") (pinfunction "2_2") (pintype "passive"))
    )
    (net (code "47") (name "Net-(C38-Pad-)") (class "Default")
      (node (ref "C38") (pin "-") (pinfunction "-_-") (pintype "passive"))
      (node (ref "SP1") (pin "1") (pinfunction "1_1") (pintype "passive"))
    )
    (net (code "48") (name "Net-(FAN-Pad2)") (class "Default")
      (node (ref "FAN") (pin "2") (pinfunction "2_2") (pintype "passive"))
      (node (ref "Q2") (pin "2") (pinfunction "D_2") (pintype "passive"))
    )
    (net (code "49") (name "Net-(GP4-P)") (class "Default")
      (node (ref "GP4") (pin "1") (pinfunction "P_1") (pintype "passive"))
      (node (ref "U$5") (pin "P1_7") (pinfunction "GPIO4/GPCLK0_P1_7") (pintype "bidirectional"))
    )
    (net (code "50") (name "Net-(GP14-P)") (class "Default")
      (node (ref "GP14") (pin "1") (pinfunction "P_1") (pintype "passive"))
      (node (ref "U$5") (pin "P1_8") (pinfunction "UART0_TXD/GPIO14_P1_8") (pintype "bidirectional"))
    )
    (net (code "51") (name "Net-(GP15-P)") (class "Default")
      (node (ref "GP15") (pin "1") (pinfunction "P_1") (pintype "passive"))
      (node (ref "U$5") (pin "P1_10") (pinfunction "UART0_RXD/GPIO15_P1_10") (pintype "bidirectional"))
    )
    (net (code "52") (name "Net-(GP22-P)") (class "Default")
      (node (ref "GP22") (pin "1") (pinfunction "P_1") (pintype "passive"))
      (node (ref "U$5") (pin "P1_15") (pinfunction "GPIO22_P1_15") (pintype "bidirectional"))
    )
    (net (code "53") (name "Net-(GP27-P)") (class "Default")
      (node (ref "GP27") (pin "1") (pinfunction "P_1") (pintype "passive"))
      (node (ref "U$5") (pin "P1_13") (pinfunction "GPIO27_P1_13") (pintype "bidirectional"))
    )
    (net (code "54") (name "Net-(IC1-+IN)") (class "Default")
      (node (ref "IC1") (pin "3") (pinfunction "+IN_3") (pintype "input"))
      (node (ref "R1") (pin "2") (pinfunction "2_2") (pintype "passive"))
      (node (ref "R5") (pin "1") (pinfunction "1_1") (pintype "passive"))
    )
    (net (code "55") (name "Net-(IC1-OUT)") (class "Default")
      (node (ref "C16") (pin "1") (pinfunction "1_1") (pintype "passive"))
      (node (ref "C38") (pin "+") (pinfunction "+_+") (pintype "passive"))
      (node (ref "IC1") (pin "5") (pinfunction "OUT_5") (pintype "output"))
    )
    (net (code "56") (name "Net-(IC2-(PCINT3{slash}ADC3)PA3)") (class "Default")
      (node (ref "IC2") (pin "34") (pinfunction "(PCINT3/ADC3)PA3_34") (pintype "bidirectional"))
      (node (ref "R48") (pin "2") (pinfunction "2_2") (pintype "passive"))
    )
    (net (code "57") (name "Net-(IC2-(PCINT5{slash}ADC5)PA5)") (class "Default")
      (node (ref "CO_CL+PU_LK") (pin "2") (pinfunction "2_2") (pintype "passive"))
      (node (ref "IC2") (pin "32") (pinfunction "(PCINT5/ADC5)PA5_32") (pintype "bidirectional"))
    )
    (net (code "58") (name "Net-(IC2-(PCINT6{slash}ADC6)PA6)") (class "Default")
      (node (ref "C_LOCK") (pin "1") (pinfunction "1_1") (pintype "passive"))
      (node (ref "IC2") (pin "31") (pinfunction "(PCINT6/ADC6)PA6_31") (pintype "bidirectional"))
    )
    (net (code "59") (name "Net-(IC2-(PCINT7{slash}ADC7)PA7)") (class "Default")
      (node (ref "CO_CL+PU_LK") (pin "1") (pinfunction "1_1") (pintype "passive"))
      (node (ref "IC2") (pin "30") (pinfunction "(PCINT7/ADC7)PA7_30") (pintype "bidirectional"))
    )
    (net (code "60") (name "Net-(IC2-(PCINT13{slash}MOSI)PB5)") (class "Default")
      (node (ref "IC2") (pin "1") (pinfunction "(PCINT13/MOSI)PB5_1") (pintype "bidirectional"))
      (node (ref "U$5") (pin "P1_12") (pinfunction "PWM0/GPIO18_P1_12") (pintype "bidirectional"))
    )
    (net (code "61") (name "Net-(IC2-(PCINT14{slash}MISO)PB6)") (class "Default")
      (node (ref "IC2") (pin "2") (pinfunction "(PCINT14/MISO)PB6_2") (pintype "bidirectional"))
      (node (ref "U$5") (pin "P1_16") (pinfunction "GPIO23_P1_16") (pintype "bidirectional"))
    )
    (net (code "62") (name "Net-(IC2-(PCINT15{slash}SCK)PB7)") (class "Default")
      (node (ref "IC2") (pin "3") (pinfunction "(PCINT15/SCK)PB7_3") (pintype "bidirectional"))
      (node (ref "U$5") (pin "P1_18") (pinfunction "GPIO24_P1_18") (pintype "bidirectional"))
    )
    (net (code "63") (name "Net-(IC2-(PCINT24{slash}RXD0)PD0)") (class "Default")
      (node (ref "IC2") (pin "9") (pinfunction "(PCINT24/RXD0)PD0_9") (pintype "bidirectional"))
      (node (ref "RX") (pin "1") (pinfunction "P_1") (pintype "passive"))
    )
    (net (code "64") (name "Net-(IC2-(PCINT25{slash}TXD0)PD1)") (class "Default")
      (node (ref "IC2") (pin "10") (pinfunction "(PCINT25/TXD0)PD1_10") (pintype "bidirectional"))
      (node (ref "TX") (pin "1") (pinfunction "P_1") (pintype "passive"))
    )
    (net (code "65") (name "Net-(IC2-(PCINT31{slash}OC2A)PD7)") (class "Default")
      (node (ref "IC2") (pin "16") (pinfunction "(PCINT31/OC2A)PD7_16") (pintype "bidirectional"))
      (node (ref "R4") (pin "2") (pinfunction "2_2") (pintype "passive"))
    )
    (net (code "66") (name "Net-(IC2-RESET)") (class "Default")
      (node (ref "AT_ON") (pin "A") (pinfunction "A_A") (pintype "passive"))
      (node (ref "C8") (pin "2") (pinfunction "2_2") (pintype "passive"))
      (node (ref "IC2") (pin "4") (pinfunction "RESET_4") (pintype "input"))
      (node (ref "R3") (pin "1") (pinfunction "1_1") (pintype "passive"))
      (node (ref "T1") (pin "C") (pinfunction "C_C") (pintype "passive"))
    )
    (net (code "67") (name "Net-(IC2-XTAL1)") (class "Default")
      (node (ref "C14") (pin "1") (pinfunction "1_1") (pintype "passive"))
      (node (ref "IC2") (pin "8") (pinfunction "XTAL1_8") (pintype "bidirectional"))
      (node (ref "Q1") (pin "1") (pinfunction "1_1") (pintype "passive"))
    )
    (net (code "68") (name "Net-(IC2-XTAL2)") (class "Default")
      (node (ref "C3") (pin "1") (pinfunction "1_1") (pintype "passive"))
      (node (ref "IC2") (pin "7") (pinfunction "XTAL2_7") (pintype "bidirectional"))
      (node (ref "Q1") (pin "2") (pinfunction "2_2") (pintype "passive"))
    )
    (net (code "69") (name "Net-(POWR_BRD-Pad12)") (class "Default")
      (node (ref "POWR_BRD") (pin "12") (pinfunction "12_12") (pintype "passive"))
      (node (ref "T3") (pin "C") (pinfunction "C_C") (pintype "passive"))
    )
    (net (code "70") (name "Net-(Q3-D-Pad2)") (class "Default")
      (node (ref "Q3") (pin "2") (pinfunction "D_2") (pintype "passive"))
      (node (ref "VALVE+PROXSW") (pin "2") (pinfunction "2_2") (pintype "passive"))
    )
    (net (code "71") (name "Net-(R8-Pad2)") (class "Default")
      (node (ref "R8") (pin "2") (pinfunction "2_2") (pintype "passive"))
      (node (ref "T1") (pin "B") (pinfunction "B_B") (pintype "passive"))
    )
    (net (code "72") (name "Net-(R9-Pad1)") (class "Default")
      (node (ref "R9") (pin "1") (pinfunction "1_1") (pintype "passive"))
      (node (ref "T3") (pin "B") (pinfunction "B_B") (pintype "passive"))
    )
    (net (code "73") (name "Net-(R13-Pad2)") (class "Default")
      (node (ref "R13") (pin "2") (pinfunction "2_2") (pintype "passive"))
      (node (ref "RPI_RST") (pin "C") (pinfunction "C_C") (pintype "passive"))
    )
    (net (code "74") (name "Net-(T2A-B)") (class "Default")
      (node (ref "R46") (pin "1") (pinfunction "1_1") (pintype "passive"))
      (node (ref "T2") (pin "2") (pinfunction "B_2") (pintype "passive"))
      (node (ref "T2") (pin "5") (pinfunction "C1_5") (pintype "passive"))
    )
    (net (code "75") (name "Net-(T2A-C1)") (class "Default")
      (node (ref "T2") (pin "8") (pinfunction "C1_8") (pintype "passive"))
      (node (ref "U$5") (pin "P1_2") (pinfunction "+5V_P1_2") (pintype "power_in"))
      (node (ref "U$5") (pin "P1_4") (pinfunction "+5V_P1_4") (pintype "power_in"))
    )
    (net (code "76") (name "Net-(T2B-B)") (class "Default")
      (node (ref "R10") (pin "2") (pinfunction "2_2") (pintype "passive"))
      (node (ref "R47") (pin "2") (pinfunction "2_2") (pintype "passive"))
      (node (ref "T2") (pin "4") (pinfunction "B_4") (pintype "passive"))
    )
    (net (code "77") (name "Net-(U$5-GPIO2{slash}I2C1_SDA)") (class "Default")
      (node (ref "I2C") (pin "2") (pinfunction "2_2") (pintype "passive"))
      (node (ref "U$5") (pin "P1_3") (pinfunction "GPIO2/I2C1_SDA_P1_3") (pintype "bidirectional"))
    )
    (net (code "78") (name "Net-(U$5-GPIO3{slash}I2C1_SCL)") (class "Default")
      (node (ref "I2C") (pin "1") (pinfunction "1_1") (pintype "passive"))
      (node (ref "U$5") (pin "P1_5") (pinfunction "GPIO3/I2C1_SCL_P1_5") (pintype "bidirectional"))
    )
    (net (code "79") (name "Net-(U$5-GPIO7{slash}SPI0_CE1)") (class "Default")
      (node (ref "BUT2+3") (pin "1") (pinfunction "1_1") (pintype "passive"))
      (node (ref "R7") (pin "2") (pinfunction "2_2") (pintype "passive"))
      (node (ref "U$5") (pin "P1_26") (pinfunction "GPIO7/SPI0_CE1_P1_26") (pintype "bidirectional"))
    )
    (net (code "80") (name "Net-(U$5-GPIO8{slash}SPI0_CE0)") (class "Default")
      (node (ref "BUT2+3") (pin "2") (pinfunction "2_2") (pintype "passive"))
      (node (ref "R6") (pin "2") (pinfunction "2_2") (pintype "passive"))
      (node (ref "U$5") (pin "P1_24") (pinfunction "GPIO8/SPI0_CE0_P1_24") (pintype "bidirectional"))
    )
    (net (code "81") (name "Net-(U$5-GPIO25)") (class "Default")
      (node (ref "R39") (pin "2") (pinfunction "2_2") (pintype "passive"))
      (node (ref "U$5") (pin "P1_22") (pinfunction "GPIO25_P1_22") (pintype "bidirectional"))
    )
    (net (code "82") (name "Net-(U$5-UART0_RTS{slash}GPIO17)") (class "Default")
      (node (ref "R8") (pin "1") (pinfunction "1_1") (pintype "passive"))
      (node (ref "U$5") (pin "P1_11") (pinfunction "UART0_RTS/GPIO17_P1_11") (pintype "bidirectional"))
    )
    (net (code "83") (name "Net-(U1-AIN1(+))") (class "Default")
      (node (ref "C20") (pin "1") (pinfunction "1_1") (pintype "passive"))
      (node (ref "C21") (pin "1") (pinfunction "1_1") (pintype "passive"))
      (node (ref "R17") (pin "1") (pinfunction "1_1") (pintype "passive"))
      (node (ref "U1") (pin "7") (pinfunction "AIN1(+)_7") (pintype "input"))
    )
    (net (code "84") (name "Net-(U1-AIN1(-))") (class "Default")
      (node (ref "C19") (pin "1") (pinfunction "1_1") (pintype "passive"))
      (node (ref "C21") (pin "2") (pinfunction "2_2") (pintype "passive"))
      (node (ref "R30") (pin "1") (pinfunction "1_1") (pintype "passive"))
      (node (ref "U1") (pin "8") (pinfunction "AIN1(-)_8") (pintype "input"))
    )
    (net (code "85") (name "Net-(U1-AIN2(+))") (class "Default")
      (node (ref "C22") (pin "1") (pinfunction "1_1") (pintype "passive"))
      (node (ref "C23") (pin "1") (pinfunction "1_1") (pintype "passive"))
      (node (ref "R31") (pin "1") (pinfunction "1_1") (pintype "passive"))
      (node (ref "U1") (pin "9") (pinfunction "AIN2(+)_9") (pintype "input"))
    )
    (net (code "86") (name "Net-(U1-AIN2(-))") (class "Default")
      (node (ref "C22") (pin "2") (pinfunction "2_2") (pintype "passive"))
      (node (ref "C24") (pin "1") (pinfunction "1_1") (pintype "passive"))
      (node (ref "R32") (pin "1") (pinfunction "1_1") (pintype "passive"))
      (node (ref "U1") (pin "10") (pinfunction "AIN2(-)_10") (pintype "input"))
    )
    (net (code "87") (name "Net-(U1-AIN3(+))") (class "Default")
      (node (ref "C26") (pin "1") (pinfunction "1_1") (pintype "passive"))
      (node (ref "C28") (pin "1") (pinfunction "1_1") (pintype "passive"))
      (node (ref "R33") (pin "1") (pinfunction "1_1") (pintype "passive"))
      (node (ref "U1") (pin "11") (pinfunction "AIN3(+)_11") (pintype "input"))
    )
    (net (code "88") (name "Net-(U1-AIN3(-))") (class "Default")
      (node (ref "C27") (pin "1") (pinfunction "1_1") (pintype "passive"))
      (node (ref "C28") (pin "2") (pinfunction "2_2") (pintype "passive"))
      (node (ref "R34") (pin "1") (pinfunction "1_1") (pintype "passive"))
      (node (ref "U1") (pin "12") (pinfunction "AIN3(-)_12") (pintype "input"))
    )
    (net (code "89") (name "Net-(U1-AIN4(+){slash}REFIN2(+))") (class "Default")
      (node (ref "C30") (pin "1") (pinfunction "1_1") (pintype "passive"))
      (node (ref "C32") (pin "1") (pinfunction "1_1") (pintype "passive"))
      (node (ref "R35") (pin "1") (pinfunction "1_1") (pintype "passive"))
      (node (ref "U1") (pin "17") (pinfunction "AIN4(+)/REFIN2(+)_17") (pintype "input"))
    )
    (net (code "90") (name "Net-(U1-AIN4(-){slash}REFIN2(-))") (class "Default")
      (node (ref "C31") (pin "1") (pinfunction "1_1") (pintype "passive"))
      (node (ref "C32") (pin "2") (pinfunction "2_2") (pintype "passive"))
      (node (ref "R36") (pin "1") (pinfunction "1_1") (pintype "passive"))
      (node (ref "U1") (pin "18") (pinfunction "AIN4(-)/REFIN2(-)_18") (pintype "input"))
    )
    (net (code "91") (name "Net-(U1-AIN5(+){slash}IOUT2)") (class "Default")
      (node (ref "C35") (pin "1") (pinfunction "1_1") (pintype "passive"))
      (node (ref "C36") (pin "1") (pinfunction "1_1") (pintype "passive"))
      (node (ref "R37") (pin "1") (pinfunction "1_1") (pintype "passive"))
      (node (ref "U1") (pin "15") (pinfunction "AIN5(+)/IOUT2_15") (pintype "bidirectional"))
    )
    (net (code "92") (name "Net-(U1-AIN5(-){slash}IOUT1)") (class "Default")
      (node (ref "C34") (pin "1") (pinfunction "1_1") (pintype "passive"))
      (node (ref "C36") (pin "2") (pinfunction "2_2") (pintype "passive"))
      (node (ref "R38") (pin "1") (pinfunction "1_1") (pintype "passive"))
      (node (ref "U1") (pin "16") (pinfunction "AIN5(-)/IOUT1_16") (pintype "bidirectional"))
    )
    (net (code "93") (name "unconnected-(IC1-BYPASS-Pad7)") (class "Default")
      (node (ref "IC1") (pin "7") (pinfunction "BYPASS_7") (pintype "passive"))
    )
    (net (code "94") (name "unconnected-(IC1-GAIN-Pad1)") (class "Default")
      (node (ref "IC1") (pin "1") (pinfunction "GAIN_1") (pintype "passive"))
    )
    (net (code "95") (name "unconnected-(IC1-GAIN-Pad8)") (class "Default")
      (node (ref "IC1") (pin "8") (pinfunction "GAIN_8") (pintype "passive"))
    )
    (net (code "96") (name "unconnected-(J3-Pad2)") (class "Default")
      (node (ref "J3") (pin "2") (pinfunction "2_2") (pintype "bidirectional"))
    )
    (net (code "97") (name "unconnected-(LC1-Pad4)") (class "Default")
      (node (ref "LC1") (pin "4") (pinfunction "4_4") (pintype "input"))
    )
    (net (code "98") (name "unconnected-(LC2-Pad4)") (class "Default")
      (node (ref "LC2") (pin "4") (pinfunction "4_4") (pintype "input"))
    )
    (net (code "99") (name "unconnected-(LC3-Pad4)") (class "Default")
      (node (ref "LC3") (pin "4") (pinfunction "4_4") (pintype "input"))
    )
    (net (code "100") (name "unconnected-(LC4-Pad4)") (class "Default")
      (node (ref "LC4") (pin "4") (pinfunction "4_4") (pintype "input"))
    )
    (net (code "101") (name "unconnected-(POWR_BRD-Pad6)") (class "Default")
      (node (ref "POWR_BRD") (pin "6") (pinfunction "6_6") (pintype "passive"))
    )
    (net (code "102") (name "unconnected-(POWR_BRD-Pad8)") (class "Default")
      (node (ref "POWR_BRD") (pin "8") (pinfunction "8_8") (pintype "passive"))
    )
    (net (code "103") (name "unconnected-(POWR_BRD-Pad9)") (class "Default")
      (node (ref "POWR_BRD") (pin "9") (pinfunction "9_9") (pintype "passive"))
    )
    (net (code "104") (name "unconnected-(POWR_BRD-Pad10)") (class "Default")
      (node (ref "POWR_BRD") (pin "10") (pinfunction "10_10") (pintype "passive"))
    )
    (net (code "105") (name "unconnected-(PRESS-Pad4)") (class "Default")
      (node (ref "PRESS") (pin "4") (pinfunction "4_4") (pintype "input"))
    )
    (net (code "106") (name "unconnected-(Q2-D-Pad4)") (class "Default")
      (node (ref "Q2") (pin "4") (pinfunction "D_4") (pintype "passive"))
    )
    (net (code "107") (name "unconnected-(Q3-D-Pad4)") (class "Default")
      (node (ref "Q3") (pin "4") (pinfunction "D_4") (pintype "passive"))
    )
    (net (code "108") (name "unconnected-(T2A-C-Pad7)") (class "Default")
      (node (ref "T2") (pin "7") (pinfunction "C_7") (pintype "passive"))
    )
    (net (code "109") (name "unconnected-(T2B-C2-Pad6)") (class "Default")
      (node (ref "T2") (pin "6") (pinfunction "C2_6") (pintype "passive"))
    )
    (net (code "110") (name "unconnected-(U1-CLK-Pad2)") (class "Default")
      (node (ref "U1") (pin "2") (pinfunction "CLK_2") (pintype "input"))
    )
    (net (code "111") (name "unconnected-(U1-NC-Pad4)") (class "Default")
      (node (ref "U1") (pin "4") (pinfunction "NC_4") (pintype "no_connect"))
    )
  )
)
